# jn5169_v1_1.net
KiCad netlist of a schematic drawn in EAGLE
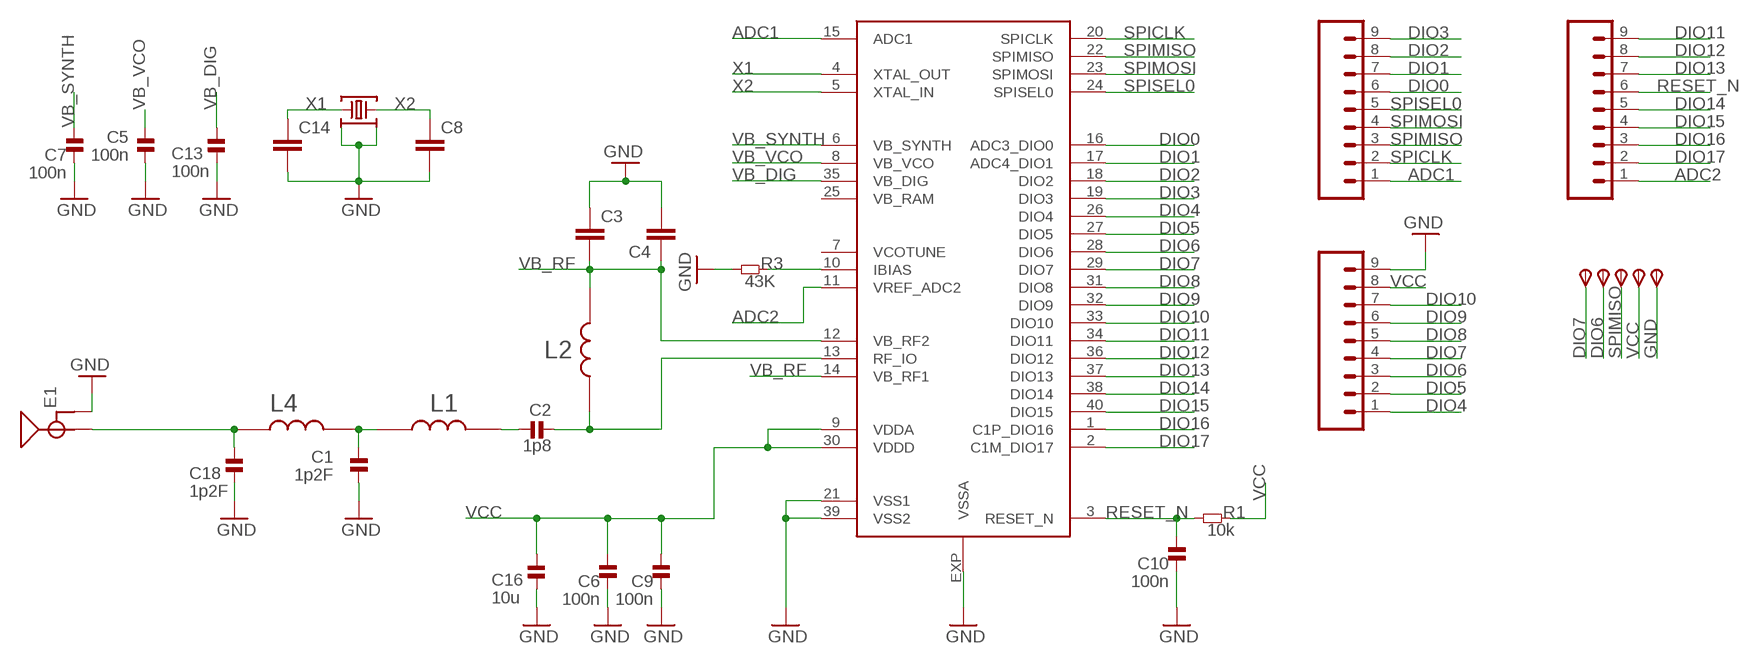
[diagram p0: schematic, sheet 1]

(export (version "E")
  (design (tool "Eeschema 10.0.6"))
  (components
    (comp (ref "C1")
      (value "1p2F")
      (footprint "eagle-import:_PKG_C_0402")
      (libsource (lib "eagle-import") (part "CAP-0402"))
    )
    (comp (ref "C2")
      (value "1p8")
      (footprint "eagle-import:_PKG_C_0402")
      (libsource (lib "eagle-import") (part "CAP-0402"))
    )
    (comp (ref "C3")
      (value "100n")
      (footprint "eagle-import:CAPC1005X40N")
      (fields (field (name "MF") "Yageo") (field (name "MP") "RC0402FR-073M6L"))
      (libsource (lib "eagle-import") (part "CAP0402"))
    )
    (comp (ref "C4")
      (value "47pf")
      (footprint "eagle-import:CAPC1005X40N")
      (fields (field (name "MF") "Yageo") (field (name "MP") "RC0402FR-073M6L"))
      (libsource (lib "eagle-import") (part "CAP0402"))
    )
    (comp (ref "C5")
      (value "100n")
      (footprint "eagle-import:_PKG_C_0402")
      (libsource (lib "eagle-import") (part "CAP-0402"))
    )
    (comp (ref "C6")
      (value "100n")
      (footprint "eagle-import:_PKG_C_0402")
      (libsource (lib "eagle-import") (part "CAP-0402"))
    )
    (comp (ref "C7")
      (value "100n")
      (footprint "eagle-import:_PKG_C_0402")
      (libsource (lib "eagle-import") (part "CAP-0402"))
    )
    (comp (ref "C8")
      (value "12p")
      (footprint "eagle-import:CAPC1005X40N")
      (fields (field (name "MF") "Yageo") (field (name "MP") "RC0402FR-073M6L"))
      (libsource (lib "eagle-import") (part "CAP0402"))
    )
    (comp (ref "C9")
      (value "100n")
      (footprint "eagle-import:_PKG_C_0402")
      (libsource (lib "eagle-import") (part "CAP-0402"))
    )
    (comp (ref "C10")
      (value "100n")
      (footprint "eagle-import:_PKG_C_0402")
      (libsource (lib "eagle-import") (part "CAP-0402"))
    )
    (comp (ref "C13")
      (value "100n")
      (footprint "eagle-import:_PKG_C_0402")
      (libsource (lib "eagle-import") (part "CAP-0402"))
    )
    (comp (ref "C14")
      (value "12p")
      (footprint "eagle-import:CAPC1005X40N")
      (fields (field (name "MF") "Yageo") (field (name "MP") "RC0402FR-073M6L"))
      (libsource (lib "eagle-import") (part "CAP0402"))
    )
    (comp (ref "C16")
      (value "10u")
      (footprint "eagle-import:_PKG_C_0805")
      (libsource (lib "eagle-import") (part "CAP-0805"))
    )
    (comp (ref "C18")
      (value "1p2F")
      (footprint "eagle-import:_PKG_C_0402")
      (libsource (lib "eagle-import") (part "CAP-0402"))
    )
    (comp (ref "E1")
      (value "ANTENNA-GROUNDEDTRACE-15.2MM")
      (footprint "eagle-import:TRACE_ANTENNA_2.4GHZ_15.2MM")
      (libsource (lib "eagle-import") (part "ANTENNA-GROUNDEDTRACE-15.2MM"))
    )
    (comp (ref "GND")
      (value "TPSTP11R")
      (footprint "eagle-import:TP11R")
      (libsource (lib "eagle-import") (part "TPSTP11R"))
    )
    (comp (ref "J1")
      (value "CONN_051.27MM")
      (footprint "eagle-import:1X05_1.27MM")
      (libsource (lib "eagle-import") (part "CONN_051.27MM"))
    )
    (comp (ref "J2")
      (value "CONN_051.27MM")
      (footprint "eagle-import:1X05_1.27MM")
      (libsource (lib "eagle-import") (part "CONN_051.27MM"))
    )
    (comp (ref "J3")
      (value "CONN_051.27MM")
      (footprint "eagle-import:1X05_1.27MM")
      (libsource (lib "eagle-import") (part "CONN_051.27MM"))
    )
    (comp (ref "L1")
      (value "3n3H")
      (footprint "eagle-import:INDC1005X40N")
      (fields (field (name "MF") "Yageo") (field (name "MP") "RC0402FR-073M6L"))
      (libsource (lib "eagle-import") (part "IND0402IND0402"))
    )
    (comp (ref "L2")
      (value "1n5H")
      (footprint "eagle-import:INDC1005X40N")
      (fields (field (name "MF") "Yageo") (field (name "MP") "RC0402FR-073M6L"))
      (libsource (lib "eagle-import") (part "IND0402IND0402"))
    )
    (comp (ref "L4")
      (value "2n7H")
      (footprint "eagle-import:INDC1005X40N")
      (fields (field (name "MF") "Yageo") (field (name "MP") "RC0402FR-073M6L"))
      (libsource (lib "eagle-import") (part "IND0402IND0402"))
    )
    (comp (ref "R1")
      (value "10k")
      (footprint "eagle-import:_PKG_C_0402")
      (libsource (lib "eagle-import") (part "RES-0402"))
    )
    (comp (ref "R3")
      (value "43K")
      (footprint "eagle-import:_PKG_C_0402")
      (libsource (lib "eagle-import") (part "RES-0402"))
    )
    (comp (ref "RX")
      (value "TPSTP11R")
      (footprint "eagle-import:TP11R")
      (libsource (lib "eagle-import") (part "TPSTP11R"))
    )
    (comp (ref "TDO")
      (value "TPSTP11R")
      (footprint "eagle-import:TP11R")
      (libsource (lib "eagle-import") (part "TPSTP11R"))
    )
    (comp (ref "TX")
      (value "TPSTP11R")
      (footprint "eagle-import:TP11R")
      (libsource (lib "eagle-import") (part "TPSTP11R"))
    )
    (comp (ref "U$1")
      (value "JN5168/A02Z")
      (footprint "eagle-import:QFN50P600X600X100-41N")
      (fields (field (name "MF") "NXP Semiconductors"))
      (libsource (lib "eagle-import") (part "JN5168/A02Z"))
    )
    (comp (ref "VCC")
      (value "TPSTP11R")
      (footprint "eagle-import:TP11R")
      (libsource (lib "eagle-import") (part "TPSTP11R"))
    )
    (comp (ref "Y1")
      (value "32MHZ")
      (footprint "eagle-import:XTAL-4P-2016")
      (fields (field (name "DIGIKEY_PART") "1253-2042-1-ND") (field (name "MFG_PART") "CX2016DB48000C0FPLC1"))
      (libsource (lib "eagle-import") (part "48.000MHZ_CX2016DB48000C0FPLC1"))
    )
  )
  (nets
    (net (code "1") (name "/ADC1") (class "Default")
      (node (ref "J1") (pin "1") (pinfunction "1_1") (pintype "passive"))
      (node (ref "U$1") (pin "15") (pinfunction "ADC1_15") (pintype "power_in"))
    )
    (net (code "2") (name "/ADC2") (class "Default")
      (node (ref "J3") (pin "1") (pinfunction "1_1") (pintype "passive"))
      (node (ref "U$1") (pin "11") (pinfunction "VREF_ADC2_11") (pintype "power_in"))
    )
    (net (code "3") (name "/DIO0") (class "Default")
      (node (ref "J1") (pin "6") (pinfunction "6_6") (pintype "passive"))
      (node (ref "U$1") (pin "16") (pinfunction "ADC3_DIO0_16") (pintype "bidirectional"))
    )
    (net (code "4") (name "/DIO1") (class "Default")
      (node (ref "J1") (pin "7") (pinfunction "7_7") (pintype "passive"))
      (node (ref "U$1") (pin "17") (pinfunction "ADC4_DIO1_17") (pintype "bidirectional"))
    )
    (net (code "5") (name "/DIO2") (class "Default")
      (node (ref "J1") (pin "8") (pinfunction "8_8") (pintype "passive"))
      (node (ref "U$1") (pin "18") (pinfunction "DIO2_18") (pintype "bidirectional"))
    )
    (net (code "6") (name "/DIO3") (class "Default")
      (node (ref "J1") (pin "9") (pinfunction "9_9") (pintype "passive"))
      (node (ref "U$1") (pin "19") (pinfunction "DIO3_19") (pintype "bidirectional"))
    )
    (net (code "7") (name "/DIO4") (class "Default")
      (node (ref "J2") (pin "1") (pinfunction "1_1") (pintype "passive"))
      (node (ref "U$1") (pin "26") (pinfunction "DIO4_26") (pintype "bidirectional"))
    )
    (net (code "8") (name "/DIO5") (class "Default")
      (node (ref "J2") (pin "2") (pinfunction "2_2") (pintype "passive"))
      (node (ref "U$1") (pin "27") (pinfunction "DIO5_27") (pintype "bidirectional"))
    )
    (net (code "9") (name "/DIO6") (class "Default")
      (node (ref "J2") (pin "3") (pinfunction "3_3") (pintype "passive"))
      (node (ref "TX") (pin "TP") (pinfunction "PP_TP") (pintype "input"))
      (node (ref "U$1") (pin "28") (pinfunction "DIO6_28") (pintype "bidirectional"))
    )
    (net (code "10") (name "/DIO7") (class "Default")
      (node (ref "J2") (pin "4") (pinfunction "4_4") (pintype "passive"))
      (node (ref "RX") (pin "TP") (pinfunction "PP_TP") (pintype "input"))
      (node (ref "U$1") (pin "29") (pinfunction "DIO7_29") (pintype "bidirectional"))
    )
    (net (code "11") (name "/DIO8") (class "Default")
      (node (ref "J2") (pin "5") (pinfunction "5_5") (pintype "passive"))
      (node (ref "U$1") (pin "31") (pinfunction "DIO8_31") (pintype "bidirectional"))
    )
    (net (code "12") (name "/DIO9") (class "Default")
      (node (ref "J2") (pin "6") (pinfunction "6_6") (pintype "passive"))
      (node (ref "U$1") (pin "32") (pinfunction "DIO9_32") (pintype "bidirectional"))
    )
    (net (code "13") (name "/DIO10") (class "Default")
      (node (ref "J2") (pin "7") (pinfunction "7_7") (pintype "passive"))
      (node (ref "U$1") (pin "33") (pinfunction "DIO10_33") (pintype "bidirectional"))
    )
    (net (code "14") (name "/DIO11") (class "Default")
      (node (ref "J3") (pin "9") (pinfunction "9_9") (pintype "passive"))
      (node (ref "U$1") (pin "34") (pinfunction "DIO11_34") (pintype "bidirectional"))
    )
    (net (code "15") (name "/DIO12") (class "Default")
      (node (ref "J3") (pin "8") (pinfunction "8_8") (pintype "passive"))
      (node (ref "U$1") (pin "36") (pinfunction "DIO12_36") (pintype "bidirectional"))
    )
    (net (code "16") (name "/DIO13") (class "Default")
      (node (ref "J3") (pin "7") (pinfunction "7_7") (pintype "passive"))
      (node (ref "U$1") (pin "37") (pinfunction "DIO13_37") (pintype "bidirectional"))
    )
    (net (code "17") (name "/DIO14") (class "Default")
      (node (ref "J3") (pin "5") (pinfunction "5_5") (pintype "passive"))
      (node (ref "U$1") (pin "38") (pinfunction "DIO14_38") (pintype "bidirectional"))
    )
    (net (code "18") (name "/DIO15") (class "Default")
      (node (ref "J3") (pin "4") (pinfunction "4_4") (pintype "passive"))
      (node (ref "U$1") (pin "40") (pinfunction "DIO15_40") (pintype "bidirectional"))
    )
    (net (code "19") (name "/DIO16") (class "Default")
      (node (ref "J3") (pin "3") (pinfunction "3_3") (pintype "passive"))
      (node (ref "U$1") (pin "1") (pinfunction "C1P_DIO16_1") (pintype "bidirectional"))
    )
    (net (code "20") (name "/DIO17") (class "Default")
      (node (ref "J3") (pin "2") (pinfunction "2_2") (pintype "passive"))
      (node (ref "U$1") (pin "2") (pinfunction "C1M_DIO17_2") (pintype "bidirectional"))
    )
    (net (code "21") (name "/RESET_N") (class "Default")
      (node (ref "C10") (pin "2") (pinfunction "2_2") (pintype "passive"))
      (node (ref "J3") (pin "6") (pinfunction "6_6") (pintype "passive"))
      (node (ref "R1") (pin "2") (pinfunction "2_2") (pintype "passive"))
      (node (ref "U$1") (pin "3") (pinfunction "RESET_N_3") (pintype "input"))
    )
    (net (code "22") (name "/SPICLK") (class "Default")
      (node (ref "J1") (pin "2") (pinfunction "2_2") (pintype "passive"))
      (node (ref "U$1") (pin "20") (pinfunction "SPICLK_20") (pintype "output"))
    )
    (net (code "23") (name "/SPIMISO") (class "Default")
      (node (ref "J1") (pin "3") (pinfunction "3_3") (pintype "passive"))
      (node (ref "TDO") (pin "TP") (pinfunction "PP_TP") (pintype "input"))
      (node (ref "U$1") (pin "22") (pinfunction "SPIMISO_22") (pintype "output"))
    )
    (net (code "24") (name "/SPIMOSI") (class "Default")
      (node (ref "J1") (pin "4") (pinfunction "4_4") (pintype "passive"))
      (node (ref "U$1") (pin "23") (pinfunction "SPIMOSI_23") (pintype "bidirectional"))
    )
    (net (code "25") (name "/SPISEL0") (class "Default")
      (node (ref "J1") (pin "5") (pinfunction "5_5") (pintype "passive"))
      (node (ref "U$1") (pin "24") (pinfunction "SPISEL0_24") (pintype "bidirectional"))
    )
    (net (code "26") (name "/VB_DIG") (class "Default")
      (node (ref "C13") (pin "1") (pinfunction "1_1") (pintype "passive"))
      (node (ref "U$1") (pin "35") (pinfunction "VB_DIG_35") (pintype "power_in"))
    )
    (net (code "27") (name "/VB_RAM") (class "Default")
      (node (ref "U$1") (pin "25") (pinfunction "VB_RAM_25") (pintype "power_in"))
    )
    (net (code "28") (name "/VB_RF") (class "Default")
      (node (ref "C3") (pin "2") (pinfunction "2_2") (pintype "passive"))
      (node (ref "C4") (pin "1") (pinfunction "1_1") (pintype "passive"))
      (node (ref "L2") (pin "2") (pinfunction "2_2") (pintype "passive"))
      (node (ref "U$1") (pin "12") (pinfunction "VB_RF2_12") (pintype "power_in"))
      (node (ref "U$1") (pin "14") (pinfunction "VB_RF1_14") (pintype "power_in"))
    )
    (net (code "29") (name "/VB_SYNTH") (class "Default")
      (node (ref "C7") (pin "2") (pinfunction "2_2") (pintype "passive"))
      (node (ref "U$1") (pin "6") (pinfunction "VB_SYNTH_6") (pintype "power_in"))
    )
    (net (code "30") (name "/VB_VCO") (class "Default")
      (node (ref "C5") (pin "2") (pinfunction "2_2") (pintype "passive"))
      (node (ref "U$1") (pin "8") (pinfunction "VB_VCO_8") (pintype "power_in"))
    )
    (net (code "31") (name "/VCC") (class "Default")
      (node (ref "C16") (pin "1") (pinfunction "1_1") (pintype "passive"))
      (node (ref "C6") (pin "2") (pinfunction "2_2") (pintype "passive"))
      (node (ref "C9") (pin "2") (pinfunction "2_2") (pintype "passive"))
      (node (ref "J2") (pin "8") (pinfunction "8_8") (pintype "passive"))
      (node (ref "R1") (pin "1") (pinfunction "1_1") (pintype "passive"))
      (node (ref "U$1") (pin "30") (pinfunction "VDDD_30") (pintype "power_in"))
      (node (ref "U$1") (pin "9") (pinfunction "VDDA_9") (pintype "power_in"))
      (node (ref "VCC") (pin "TP") (pinfunction "PP_TP") (pintype "input"))
    )
    (net (code "32") (name "/VCOTUNE") (class "Default")
      (node (ref "U$1") (pin "7") (pinfunction "VCOTUNE_7") (pintype "power_in"))
    )
    (net (code "33") (name "/X1") (class "Default")
      (node (ref "C14") (pin "1") (pinfunction "1_1") (pintype "passive"))
      (node (ref "U$1") (pin "4") (pinfunction "XTAL_OUT_4") (pintype "output"))
      (node (ref "Y1") (pin "1") (pinfunction "1_1") (pintype "passive"))
    )
    (net (code "34") (name "/X2") (class "Default")
      (node (ref "C8") (pin "1") (pinfunction "1_1") (pintype "passive"))
      (node (ref "U$1") (pin "5") (pinfunction "XTAL_IN_5") (pintype "input"))
      (node (ref "Y1") (pin "3") (pinfunction "3_3") (pintype "passive"))
    )
    (net (code "35") (name "GND") (class "Default")
      (node (ref "C1") (pin "1") (pinfunction "1_1") (pintype "passive"))
      (node (ref "C10") (pin "1") (pinfunction "1_1") (pintype "passive"))
      (node (ref "C13") (pin "2") (pinfunction "2_2") (pintype "passive"))
      (node (ref "C14") (pin "2") (pinfunction "2_2") (pintype "passive"))
      (node (ref "C16") (pin "2") (pinfunction "2_2") (pintype "passive"))
      (node (ref "C18") (pin "2") (pinfunction "2_2") (pintype "passive"))
      (node (ref "C3") (pin "1") (pinfunction "1_1") (pintype "passive"))
      (node (ref "C4") (pin "2") (pinfunction "2_2") (pintype "passive"))
      (node (ref "C5") (pin "1") (pinfunction "1_1") (pintype "passive"))
      (node (ref "C6") (pin "1") (pinfunction "1_1") (pintype "passive"))
      (node (ref "C7") (pin "1") (pinfunction "1_1") (pintype "passive"))
      (node (ref "C8") (pin "2") (pinfunction "2_2") (pintype "passive"))
      (node (ref "C9") (pin "1") (pinfunction "1_1") (pintype "passive"))
      (node (ref "E1") (pin "GND") (pinfunction "GND_GND") (pintype "bidirectional"))
      (node (ref "GND") (pin "TP") (pinfunction "PP_TP") (pintype "input"))
      (node (ref "J2") (pin "9") (pinfunction "9_9") (pintype "passive"))
      (node (ref "R3") (pin "2") (pinfunction "2_2") (pintype "passive"))
      (node (ref "U$1") (pin "21") (pinfunction "VSS1_21") (pintype "power_in"))
      (node (ref "U$1") (pin "39") (pinfunction "VSS2_39") (pintype "power_in"))
      (node (ref "U$1") (pin "EXP") (pinfunction "VSSA_EXP") (pintype "power_in"))
      (node (ref "Y1") (pin "2") (pinfunction "2_2") (pintype "bidirectional"))
      (node (ref "Y1") (pin "4") (pinfunction "4_4") (pintype "bidirectional"))
    )
    (net (code "36") (name "Net-(C1-Pad2)") (class "Default")
      (node (ref "C1") (pin "2") (pinfunction "2_2") (pintype "passive"))
      (node (ref "L1") (pin "1") (pinfunction "1_1") (pintype "passive"))
      (node (ref "L4") (pin "2") (pinfunction "2_2") (pintype "passive"))
    )
    (net (code "37") (name "Net-(C2-Pad2)") (class "Default")
      (node (ref "C2") (pin "2") (pinfunction "2_2") (pintype "passive"))
      (node (ref "L1") (pin "2") (pinfunction "2_2") (pintype "passive"))
    )
    (net (code "38") (name "Net-(E1-SIGNAL)") (class "Default")
      (node (ref "C18") (pin "1") (pinfunction "1_1") (pintype "passive"))
      (node (ref "E1") (pin "ANT") (pinfunction "SIGNAL_ANT") (pintype "bidirectional"))
      (node (ref "L4") (pin "1") (pinfunction "1_1") (pintype "passive"))
    )
    (net (code "39") (name "Net-(U$1-IBIAS)") (class "Default")
      (node (ref "R3") (pin "1") (pinfunction "1_1") (pintype "passive"))
      (node (ref "U$1") (pin "10") (pinfunction "IBIAS_10") (pintype "input"))
    )
    (net (code "40") (name "Net-(U$1-RF_IO)") (class "Default")
      (node (ref "C2") (pin "1") (pinfunction "1_1") (pintype "passive"))
      (node (ref "L2") (pin "1") (pinfunction "1_1") (pintype "passive"))
      (node (ref "U$1") (pin "13") (pinfunction "RF_IO_13") (pintype "input"))
    )
  )
)
